# Power_Distribution_Board.net
KiCad netlist of a schematic drawn in Altium Designer
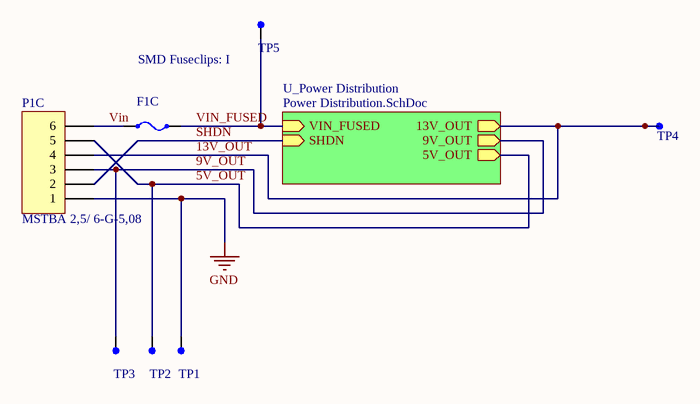
[diagram p0: Power Distribution Board.SchDoc]

(export (version "E")
  (design (tool "Eeschema 10.0.6"))
  (components
    (comp (ref "F1C")
      (value "3569TR")
      (footprint "Horizontal SMD fuse clip")
      (description "Fuse Clip Assembly")
      (libsource (lib "Keystone SchLib") (part "3569TR"))
    )
    (comp (ref "i1C")
      (value "3569TR (Placeholder)")
      (description "Fuse Clip")
      (fields (field (name "MANUFACTURER PART NUMBER") "3569TR"))
      (libsource (lib "Keystone SchLib") (part "3569TR (Placeholder)"))
    )
    (comp (ref "P1C")
      (value "MSTBA 2,5/ 6-G-5,08")
      (footprint "MSTBA 2,5 6-G-5,08")
      (description "Header, 6-Pin")
      (fields (field (name "MANUFACTURER PART NUMBER") "1757284"))
      (libsource (lib "Phoenix Contact") (part "MSTBA 2,5/ 6-G-5,08"))
    )
    (comp (ref "TP1") (value "Test Point") (footprint "TP1") (libsource (lib "URC_Lib") (part "TestPoint")))
    (comp (ref "TP2") (value "Test Point") (footprint "TP1") (libsource (lib "URC_Lib") (part "TestPoint")))
    (comp (ref "TP3") (value "Test Point") (footprint "TP1") (libsource (lib "URC_Lib") (part "TestPoint")))
    (comp (ref "TP4") (value "Test Point") (footprint "TP1") (libsource (lib "URC_Lib") (part "TestPoint")))
    (comp (ref "TP5") (value "Test Point") (footprint "TP1") (libsource (lib "URC_Lib") (part "TestPoint")))
  )
  (nets
    (net (code "1") (name "/5V_OUT") (class "Default")
      (node (ref "P1C") (pin "5") (pinfunction "5_5") (pintype "passive"))
      (node (ref "TP2") (pin "1") (pinfunction "1_1") (pintype "passive"))
    )
    (net (code "2") (name "/9V_OUT") (class "Default")
      (node (ref "P1C") (pin "3") (pinfunction "3_3") (pintype "passive"))
      (node (ref "TP3") (pin "1") (pinfunction "1_1") (pintype "passive"))
    )
    (net (code "3") (name "/13V_OUT") (class "Default")
      (node (ref "P1C") (pin "4") (pinfunction "4_4") (pintype "passive"))
      (node (ref "TP4") (pin "1") (pinfunction "1_1") (pintype "passive"))
    )
    (net (code "4") (name "/SHDN") (class "Default")
      (node (ref "P1C") (pin "2") (pinfunction "2_2") (pintype "passive"))
    )
    (net (code "5") (name "/VIN_FUSED") (class "Default")
      (node (ref "F1C") (pin "2") (pinfunction "2_2") (pintype "passive"))
      (node (ref "TP5") (pin "1") (pinfunction "1_1") (pintype "passive"))
    )
    (net (code "6") (name "/Vin") (class "Default")
      (node (ref "F1C") (pin "1") (pinfunction "1_1") (pintype "passive"))
      (node (ref "P1C") (pin "6") (pinfunction "6_6") (pintype "passive"))
    )
    (net (code "7") (name "GND") (class "Default")
      (node (ref "P1C") (pin "1") (pinfunction "1_1") (pintype "passive"))
      (node (ref "TP1") (pin "1") (pinfunction "1_1") (pintype "passive"))
    )
  )
)
